# X-M3P1O5__main_V1_0.net
KiCad netlist of a schematic drawn in Altium Designer
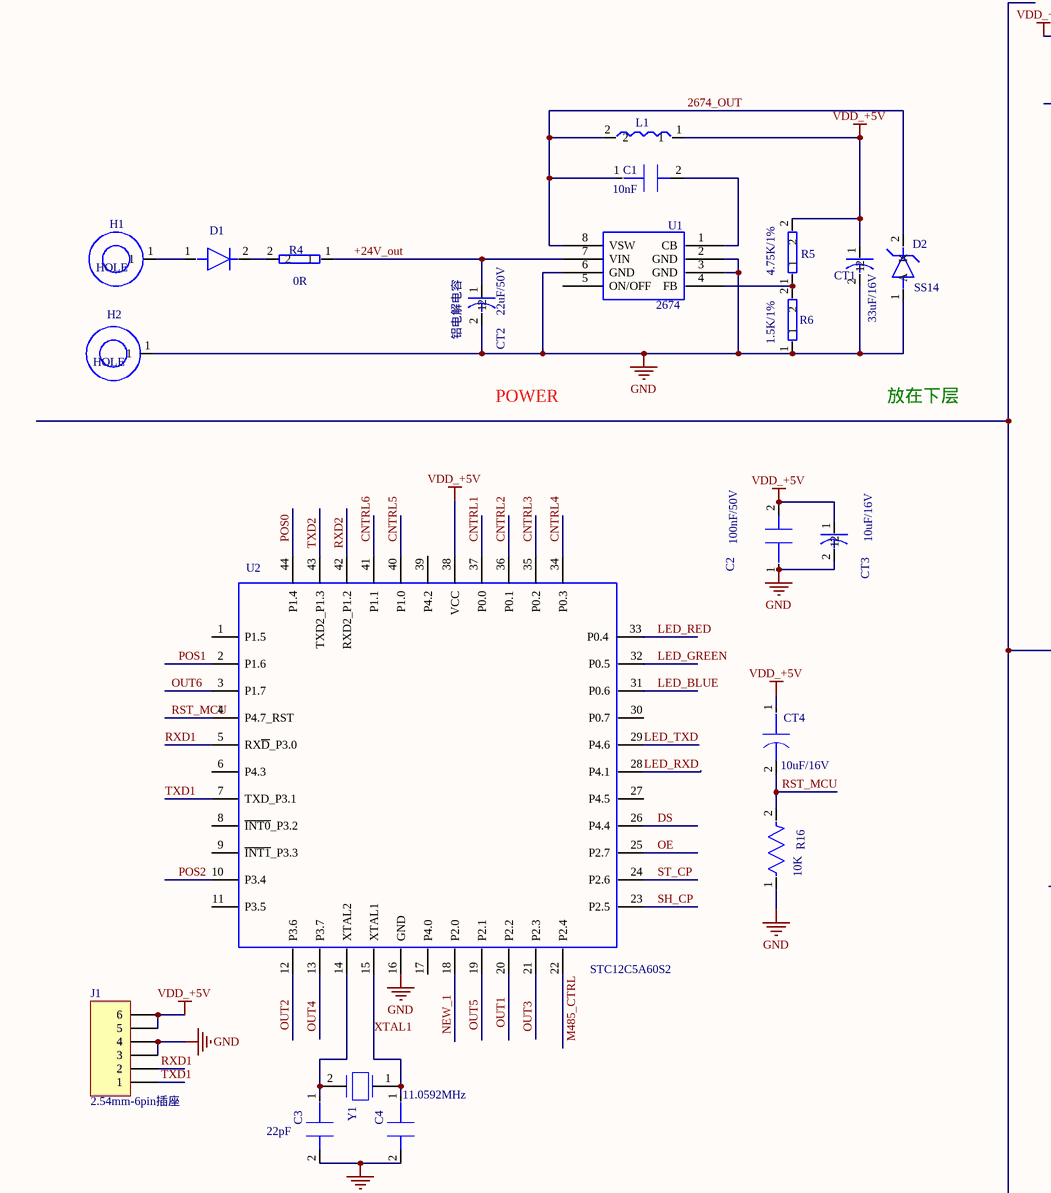
[diagram p0: X-M3P1O5__main_V1.0.SchDoc, top left]
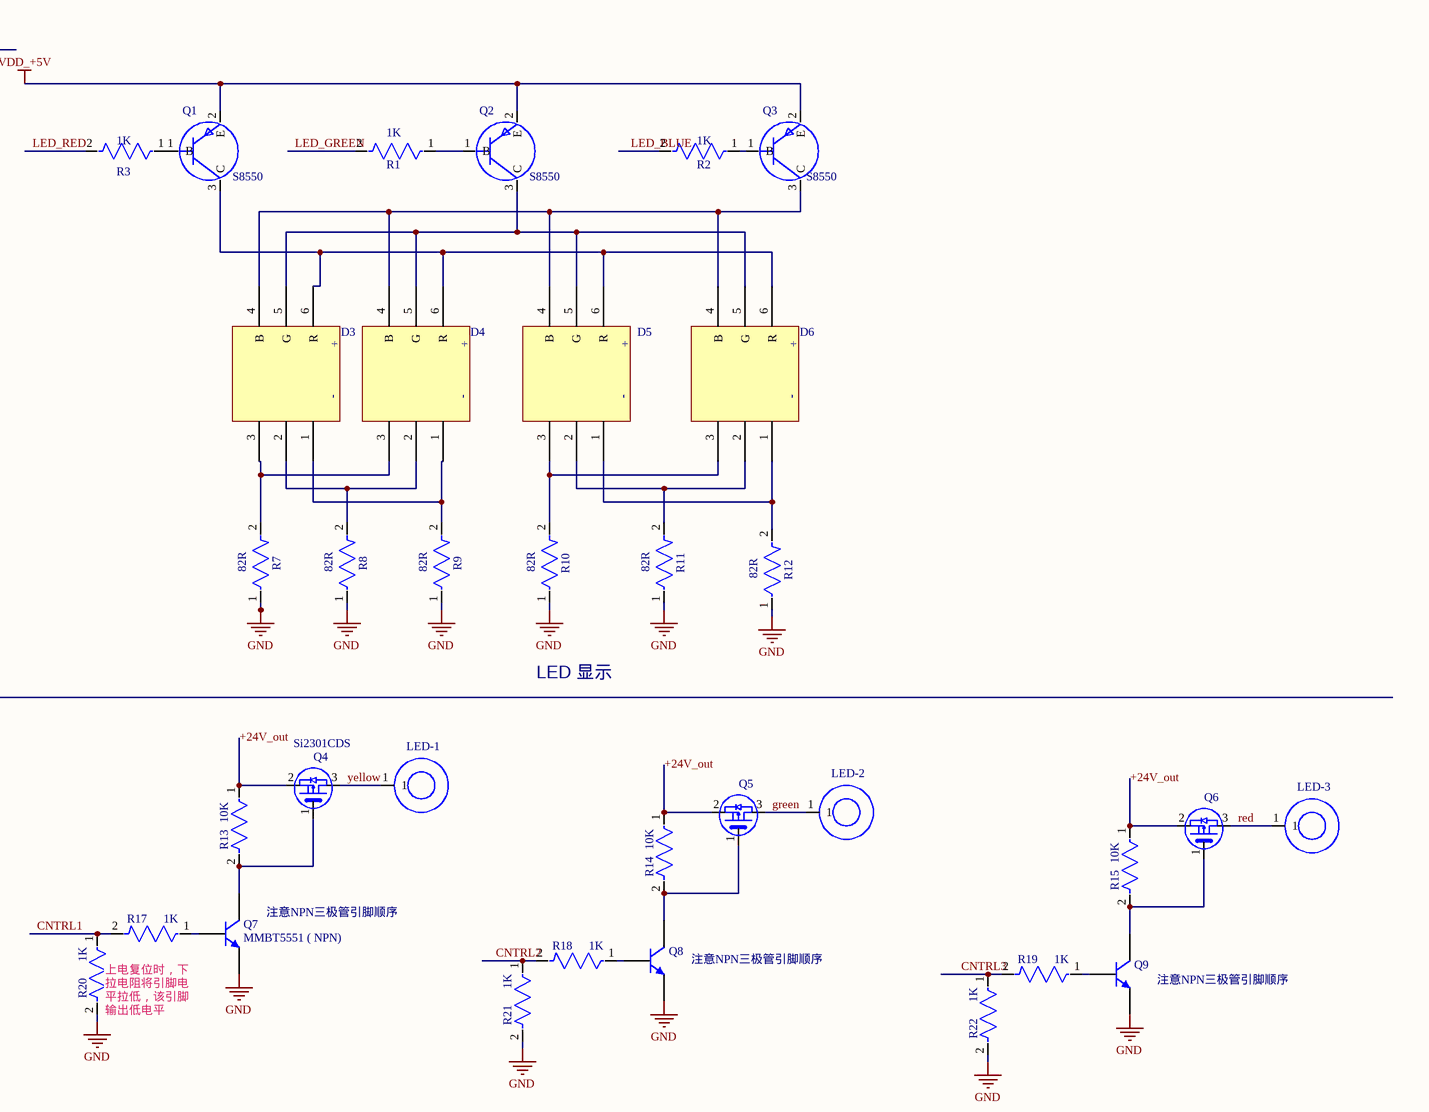
[diagram p1: X-M3P1O5__main_V1.0.SchDoc, top right]
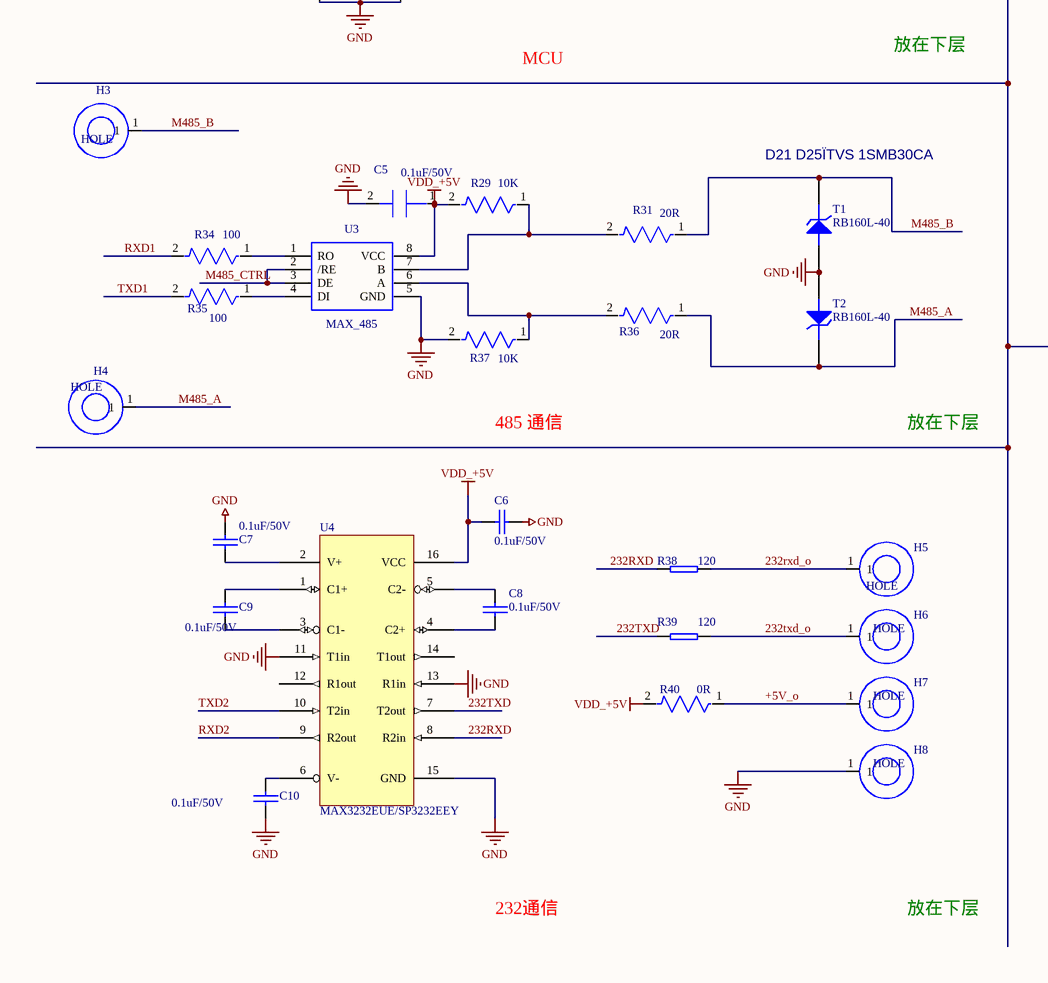
[diagram p2: X-M3P1O5__main_V1.0.SchDoc, bottom left]
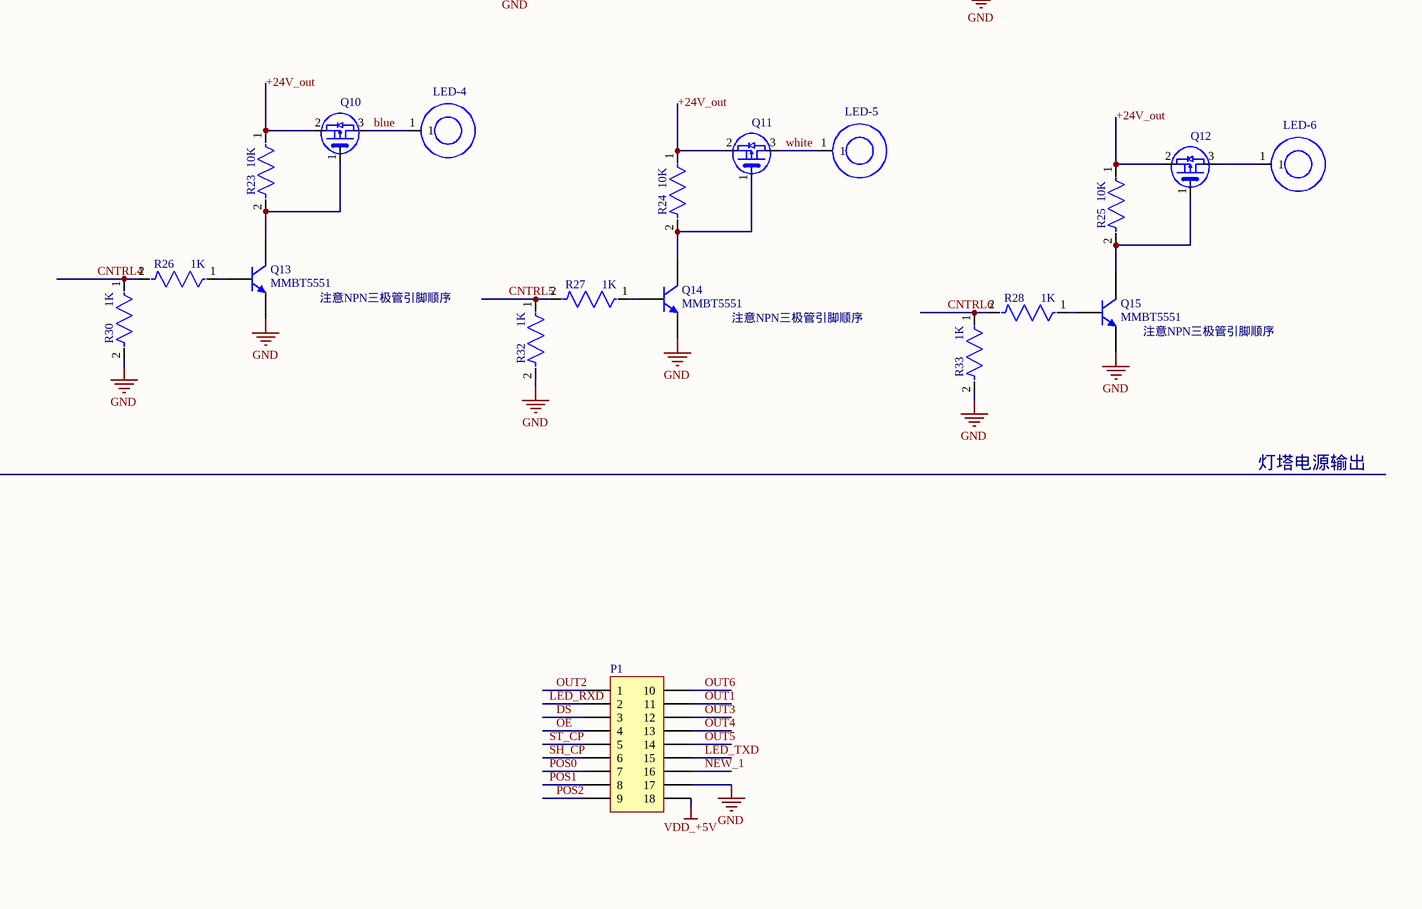
[diagram p3: X-M3P1O5__main_V1.0.SchDoc, bottom right]

(export (version "E")
  (design (tool "Eeschema 10.0.6"))
  (components
    (comp (ref "C1")
      (value "10nF")
      (footprint "MODBUS_V1.0:C0603")
      (description "SURFACE MOUNT CAPACITOR 0.031 X 0.061 INCHES")
      (fields (field (name "Comment") "CAP0603"))
      (libsource (lib "") (part "CAP0603_1"))
    )
    (comp (ref "C2")
      (value "100nF/50V")
      (footprint "MODBUS_V1.0:C0603")
      (description "SURFACE MOUNT CAPACITOR 0.031 X 0.061 INCHES")
      (fields (field (name "Comment") "CAP0603"))
      (libsource (lib "*") (part "CAP0603"))
    )
    (comp (ref "C3")
      (value "22pF")
      (footprint "C0603")
      (description "SURFACE MOUNT CAPACITOR 0.031 X 0.061 INCHES")
      (fields (field (name "Comment") "22pF/50V"))
      (libsource (lib "*") (part "CAP0603"))
    )
    (comp (ref "C4")
      (value "22pF/50V")
      (footprint "C0603")
      (description "SURFACE MOUNT CAPACITOR 0.031 X 0.061 INCHES")
      (libsource (lib "*") (part "CAP0603"))
    )
    (comp (ref "C5")
      (value "0.1uF/50V")
      (footprint "0603")
      (description "SURFACE MOUNT CAPACITOR 0.031 X 0.061 INCHES")
      (libsource (lib "") (part "CAP0603_1"))
    )
    (comp (ref "C6")
      (value "0.1uF/50V")
      (footprint "0603")
      (description "Capacitor")
      (libsource (lib "*") (part "CAP"))
    )
    (comp (ref "C7")
      (value "0.1uF/50V")
      (footprint "0603")
      (description "Capacitor")
      (libsource (lib "*") (part "CAP"))
    )
    (comp (ref "C8")
      (value "0.1uF/50V")
      (footprint "0603")
      (description "Capacitor")
      (libsource (lib "*") (part "CAP"))
    )
    (comp (ref "C9")
      (value "0.1uF/50V")
      (footprint "0603")
      (description "Capacitor")
      (libsource (lib "*") (part "CAP"))
    )
    (comp (ref "C10")
      (value "0.1uF/50V")
      (footprint "0603")
      (description "Capacitor")
      (libsource (lib "*") (part "CAP"))
    )
    (comp (ref "CT1")
      (value "33uF/16V")
      (footprint "MODBUS_V1.0:CT3528")
      (fields (field (name "Comment") "CE"))
      (libsource (lib "*") (part "CE"))
    )
    (comp (ref "CT2")
      (value "铝电解电容")
      (footprint "钱库:RB0.1")
      (fields (field (name "ALTIUM_VALUE") "22uF/50V"))
      (libsource (lib "*") (part "CE"))
    )
    (comp (ref "CT3") (value "10uF/16V") (footprint "钱库:1206C") (libsource (lib "*") (part "CE")))
    (comp (ref "CT4")
      (value "10uF/16V")
      (footprint "钱库:1206C")
      (description "SURFACE MOUNT CAPACITOR 0.048 X 0.079 INCHES")
      (libsource (lib "*") (part "CT"))
    )
    (comp (ref "D1")
      (value "M7")
      (footprint "SMB")
      (description "SURFACE MOUNT DIODE, MELF (SOD-80)")
      (libsource (lib "*") (part "DIO-MLL34"))
    )
    (comp (ref "D2") (value "SS14") (footprint "SMB") (libsource (lib "*") (part "DIOZ")))
    (comp (ref "D3")
      (value "5050RGB")
      (footprint "MODBUS_V1.0:5050RGB")
      (libsource (lib "MODBUS_V1.0") (part "5050RGB"))
    )
    (comp (ref "D4")
      (value "5050RGB")
      (footprint "MODBUS_V1.0:5050RGB")
      (libsource (lib "MODBUS_V1.0") (part "5050RGB"))
    )
    (comp (ref "D5")
      (value "5050RGB")
      (footprint "MODBUS_V1.0:5050RGB")
      (libsource (lib "MODBUS_V1.0") (part "5050RGB"))
    )
    (comp (ref "D6")
      (value "5050RGB")
      (footprint "MODBUS_V1.0:5050RGB")
      (libsource (lib "MODBUS_V1.0") (part "5050RGB"))
    )
    (comp (ref "H1") (value "HOLE") (footprint "HOLE_SMD") (libsource (lib "MODBUS_V1.0") (part "HOLE")))
    (comp (ref "H2") (value "HOLE") (footprint "HOLE_SMD") (libsource (lib "MODBUS_V1.0") (part "HOLE")))
    (comp (ref "H3") (value "HOLE") (footprint "HOLE_SMD") (libsource (lib "MODBUS_V1.0") (part "HOLE")))
    (comp (ref "H4") (value "HOLE") (footprint "HOLE_SMD") (libsource (lib "MODBUS_V1.0") (part "HOLE")))
    (comp (ref "H5") (value "HOLE") (footprint "HOLE_SMD") (libsource (lib "MODBUS_V1.0") (part "HOLE")))
    (comp (ref "H6") (value "HOLE") (footprint "HOLE_SMD") (libsource (lib "MODBUS_V1.0") (part "HOLE")))
    (comp (ref "H7") (value "HOLE") (footprint "HOLE_SMD") (libsource (lib "MODBUS_V1.0") (part "HOLE")))
    (comp (ref "H8") (value "HOLE") (footprint "HOLE_SMD") (libsource (lib "MODBUS_V1.0") (part "HOLE")))
    (comp (ref "J1")
      (value "2.54mm-6pin插座")
      (footprint "HDR1X6")
      (description "Header, 6-Pin")
      (fields (field (name "PUBLISHER") "Altium Limited"))
      (libsource (lib "Miscellaneous Connectors") (part "Header 6"))
    )
    (comp (ref "L1") (value "FB") (footprint "MODBUS_V1.0:L-6X6") (libsource (lib "*") (part "FB")))
    (comp (ref "LED-1") (value "LED_4") (footprint "HOLE_SMD") (libsource (lib "*") (part "HOLE")))
    (comp (ref "LED-2") (value "LED_4") (footprint "HOLE_SMD") (libsource (lib "*") (part "HOLE")))
    (comp (ref "LED-3") (value "LED_4") (footprint "HOLE_SMD") (libsource (lib "*") (part "HOLE")))
    (comp (ref "LED-4") (value "LED_4") (footprint "HOLE_SMD") (libsource (lib "*") (part "HOLE")))
    (comp (ref "LED-5") (value "LED_4") (footprint "HOLE_SMD") (libsource (lib "*") (part "HOLE")))
    (comp (ref "LED-6") (value "LED_4") (footprint "HOLE_SMD") (libsource (lib "*") (part "HOLE")))
    (comp (ref "P1")
      (value "Header 9X2A")
      (footprint "HDR2X9_CEN")
      (description "Header, 9-Pin, Dual row")
      (fields (field (name "PUBLISHER") "Altium Limited"))
      (libsource (lib "Miscellaneous Connectors") (part "Header 9X2A"))
    )
    (comp (ref "Q1")
      (value "S8550")
      (footprint "MODBUS_V1.0:SOT-23")
      (description "QUAD AMPLIFIER SWITCHING PNP SILICON TRANSISTOR")
      (fields (field (name "PART NUMBER") "2N3906"))
      (libsource (lib "*") (part "PNP(SOT-23)"))
    )
    (comp (ref "Q2")
      (value "S8550")
      (footprint "SOT-23")
      (description "QUAD AMPLIFIER SWITCHING PNP SILICON TRANSISTOR")
      (fields (field (name "PART NUMBER") "2N3906"))
      (libsource (lib "*") (part "S8550"))
    )
    (comp (ref "Q3")
      (value "S8550")
      (footprint "SOT-23")
      (description "QUAD AMPLIFIER SWITCHING PNP SILICON TRANSISTOR")
      (fields (field (name "PART NUMBER") "2N3906"))
      (libsource (lib "*") (part "S8550"))
    )
    (comp (ref "Q4") (value "Si2301CDS") (footprint "SOT-23") (libsource (lib "BATTERY") (part "P-MOSFET")))
    (comp (ref "Q5") (value "Si2301CDS") (footprint "SOT-23") (libsource (lib "BATTERY") (part "P-MOSFET")))
    (comp (ref "Q6") (value "Si2301CDS") (footprint "SOT-23") (libsource (lib "BATTERY") (part "P-MOSFET")))
    (comp (ref "Q7")
      (value "MMBT5551 ( NPN)")
      (footprint "SOT-23")
      (description "NPN Bipolar Transistor")
      (fields (field (name "PUBLISHER") "Altium Limited"))
      (libsource (lib "Miscellaneous Devices") (part "NPN"))
    )
    (comp (ref "Q8")
      (value "MMBT5551")
      (footprint "SOT-23")
      (description "NPN Bipolar Transistor")
      (fields (field (name "PUBLISHER") "Altium Limited"))
      (libsource (lib "Miscellaneous Devices") (part "NPN"))
    )
    (comp (ref "Q9")
      (value "MMBT5551")
      (footprint "SOT-23")
      (description "NPN Bipolar Transistor")
      (fields (field (name "PUBLISHER") "Altium Limited"))
      (libsource (lib "Miscellaneous Devices") (part "NPN"))
    )
    (comp (ref "Q10") (value "Si2301CDS") (footprint "SOT-23") (libsource (lib "BATTERY") (part "P-MOSFET")))
    (comp (ref "Q11") (value "Si2301CDS") (footprint "SOT-23") (libsource (lib "BATTERY") (part "P-MOSFET")))
    (comp (ref "Q12") (value "Si2301CDS") (footprint "SOT-23") (libsource (lib "BATTERY") (part "P-MOSFET")))
    (comp (ref "Q13")
      (value "MMBT5551")
      (footprint "SOT-23")
      (description "NPN Bipolar Transistor")
      (fields (field (name "PUBLISHER") "Altium Limited"))
      (libsource (lib "Miscellaneous Devices") (part "NPN"))
    )
    (comp (ref "Q14")
      (value "MMBT5551")
      (footprint "SOT-23")
      (description "NPN Bipolar Transistor")
      (fields (field (name "PUBLISHER") "Altium Limited"))
      (libsource (lib "Miscellaneous Devices") (part "NPN"))
    )
    (comp (ref "Q15")
      (value "MMBT5551")
      (footprint "SOT-23")
      (description "NPN Bipolar Transistor")
      (fields (field (name "PUBLISHER") "Altium Limited"))
      (libsource (lib "Miscellaneous Devices") (part "NPN"))
    )
    (comp (ref "R1")
      (value "1K")
      (footprint "MODBUS_V1.0:R0603")
      (description "SURFACE MOUNT RESISTOR 0.031 X 0.061 INCHES, 1/10W")
      (fields (field (name "Comment") "RES0603"))
      (libsource (lib "*") (part "RES0603"))
    )
    (comp (ref "R2")
      (value "1K")
      (footprint "MODBUS_V1.0:R0603")
      (description "SURFACE MOUNT RESISTOR 0.031 X 0.061 INCHES, 1/10W")
      (fields (field (name "Comment") "RES0603"))
      (libsource (lib "*") (part "RES0603"))
    )
    (comp (ref "R3")
      (value "1K")
      (footprint "MODBUS_V1.0:R0603")
      (description "SURFACE MOUNT RESISTOR 0.031 X 0.061 INCHES, 1/10W")
      (fields (field (name "Comment") "RES0603"))
      (libsource (lib "*") (part "RES0603"))
    )
    (comp (ref "R4") (value "0R") (footprint "钱库:1206") (libsource (lib "") (part "RES_1")))
    (comp (ref "R5") (value "4.75K/1%") (footprint "MODBUS_V1.0:R0603") (libsource (lib "*") (part "RES")))
    (comp (ref "R6") (value "1.5K/1%") (footprint "MODBUS_V1.0:R0603") (libsource (lib "*") (part "RES")))
    (comp (ref "R7")
      (value "82R")
      (footprint "1206")
      (description "SURFACE MOUNT RESISTOR 0.031 X 0.061 INCHES, 1/10W")
      (libsource (lib "*") (part "RES0603"))
    )
    (comp (ref "R8")
      (value "82R")
      (footprint "钱库:1206")
      (description "SURFACE MOUNT RESISTOR 0.031 X 0.061 INCHES, 1/10W")
      (libsource (lib "*") (part "RES0603"))
    )
    (comp (ref "R9")
      (value "82R")
      (footprint "钱库:1206")
      (description "SURFACE MOUNT RESISTOR 0.031 X 0.061 INCHES, 1/10W")
      (libsource (lib "*") (part "RES0603"))
    )
    (comp (ref "R10")
      (value "82R")
      (footprint "钱库:1206")
      (description "SURFACE MOUNT RESISTOR 0.031 X 0.061 INCHES, 1/10W")
      (libsource (lib "*") (part "RES0603"))
    )
    (comp (ref "R11")
      (value "82R")
      (footprint "钱库:1206")
      (description "SURFACE MOUNT RESISTOR 0.031 X 0.061 INCHES, 1/10W")
      (libsource (lib "*") (part "RES0603"))
    )
    (comp (ref "R12")
      (value "82R")
      (footprint "钱库:1206")
      (description "SURFACE MOUNT RESISTOR 0.031 X 0.061 INCHES, 1/10W")
      (libsource (lib "*") (part "RES0603"))
    )
    (comp (ref "R13")
      (value "10K")
      (footprint "R0603")
      (description "SURFACE MOUNT RESISTOR 0.031 X 0.061 INCHES, 1/10W")
      (libsource (lib "*") (part "RES0603"))
    )
    (comp (ref "R14")
      (value "10K")
      (footprint "R0603")
      (description "SURFACE MOUNT RESISTOR 0.031 X 0.061 INCHES, 1/10W")
      (libsource (lib "*") (part "RES0603"))
    )
    (comp (ref "R15")
      (value "10K")
      (footprint "R0603")
      (description "SURFACE MOUNT RESISTOR 0.031 X 0.061 INCHES, 1/10W")
      (libsource (lib "*") (part "RES0603"))
    )
    (comp (ref "R16")
      (value "10K")
      (footprint "R0603")
      (description "SURFACE MOUNT RESISTOR 0.031 X 0.061 INCHES, 1/10W")
      (libsource (lib "*") (part "RES0603"))
    )
    (comp (ref "R17")
      (value "1K")
      (footprint "R0603")
      (description "SURFACE MOUNT RESISTOR 0.031 X 0.061 INCHES, 1/10W")
      (libsource (lib "*") (part "RES0603"))
    )
    (comp (ref "R18")
      (value "1K")
      (footprint "R0603")
      (description "SURFACE MOUNT RESISTOR 0.031 X 0.061 INCHES, 1/10W")
      (libsource (lib "*") (part "RES0603"))
    )
    (comp (ref "R19")
      (value "1K")
      (footprint "R0603")
      (description "SURFACE MOUNT RESISTOR 0.031 X 0.061 INCHES, 1/10W")
      (libsource (lib "*") (part "RES0603"))
    )
    (comp (ref "R20")
      (value "1K")
      (footprint "R0603")
      (description "SURFACE MOUNT RESISTOR 0.031 X 0.061 INCHES, 1/10W")
      (libsource (lib "*") (part "RES0603"))
    )
    (comp (ref "R21")
      (value "1K")
      (footprint "R0603")
      (description "SURFACE MOUNT RESISTOR 0.031 X 0.061 INCHES, 1/10W")
      (libsource (lib "*") (part "RES0603"))
    )
    (comp (ref "R22")
      (value "1K")
      (footprint "R0603")
      (description "SURFACE MOUNT RESISTOR 0.031 X 0.061 INCHES, 1/10W")
      (libsource (lib "*") (part "RES0603"))
    )
    (comp (ref "R23")
      (value "10K")
      (footprint "R0603")
      (description "SURFACE MOUNT RESISTOR 0.031 X 0.061 INCHES, 1/10W")
      (libsource (lib "*") (part "RES0603"))
    )
    (comp (ref "R24")
      (value "10K")
      (footprint "R0603")
      (description "SURFACE MOUNT RESISTOR 0.031 X 0.061 INCHES, 1/10W")
      (libsource (lib "*") (part "RES0603"))
    )
    (comp (ref "R25")
      (value "10K")
      (footprint "R0603")
      (description "SURFACE MOUNT RESISTOR 0.031 X 0.061 INCHES, 1/10W")
      (libsource (lib "*") (part "RES0603"))
    )
    (comp (ref "R26")
      (value "1K")
      (footprint "R0603")
      (description "SURFACE MOUNT RESISTOR 0.031 X 0.061 INCHES, 1/10W")
      (libsource (lib "*") (part "RES0603"))
    )
    (comp (ref "R27")
      (value "1K")
      (footprint "R0603")
      (description "SURFACE MOUNT RESISTOR 0.031 X 0.061 INCHES, 1/10W")
      (libsource (lib "*") (part "RES0603"))
    )
    (comp (ref "R28")
      (value "1K")
      (footprint "R0603")
      (description "SURFACE MOUNT RESISTOR 0.031 X 0.061 INCHES, 1/10W")
      (libsource (lib "*") (part "RES0603"))
    )
    (comp (ref "R29")
      (value "10K")
      (footprint "R0603")
      (description "SURFACE MOUNT RESISTOR 0.031 X 0.061 INCHES, 1/10W")
      (libsource (lib "*") (part "RES0603"))
    )
    (comp (ref "R30")
      (value "1K")
      (footprint "R0603")
      (description "SURFACE MOUNT RESISTOR 0.031 X 0.061 INCHES, 1/10W")
      (libsource (lib "*") (part "RES0603"))
    )
    (comp (ref "R31")
      (value "20R")
      (footprint "MODBUS_V2.0:1206")
      (description "SURFACE MOUNT RESISTOR 0.031 X 0.061 INCHES, 1/10W")
      (libsource (lib "*") (part "RES0603"))
    )
    (comp (ref "R32")
      (value "1K")
      (footprint "R0603")
      (description "SURFACE MOUNT RESISTOR 0.031 X 0.061 INCHES, 1/10W")
      (libsource (lib "*") (part "RES0603"))
    )
    (comp (ref "R33")
      (value "1K")
      (footprint "R0603")
      (description "SURFACE MOUNT RESISTOR 0.031 X 0.061 INCHES, 1/10W")
      (libsource (lib "*") (part "RES0603"))
    )
    (comp (ref "R34")
      (value "100")
      (footprint "R0603")
      (description "SURFACE MOUNT RESISTOR 0.031 X 0.061 INCHES, 1/10W")
      (libsource (lib "*") (part "RES0603"))
    )
    (comp (ref "R35")
      (value "100")
      (footprint "R0603")
      (description "SURFACE MOUNT RESISTOR 0.031 X 0.061 INCHES, 1/10W")
      (libsource (lib "*") (part "RES0603"))
    )
    (comp (ref "R36")
      (value "20R")
      (footprint "2010")
      (description "SURFACE MOUNT RESISTOR 0.031 X 0.061 INCHES, 1/10W")
      (libsource (lib "*") (part "RES0603"))
    )
    (comp (ref "R37")
      (value "10K")
      (footprint "R0603")
      (description "SURFACE MOUNT RESISTOR 0.031 X 0.061 INCHES, 1/10W")
      (libsource (lib "*") (part "RES0603"))
    )
    (comp (ref "R38") (value "120") (footprint "R0603") (libsource (lib "*") (part "Component_1")))
    (comp (ref "R39") (value "120") (footprint "R0603") (libsource (lib "*") (part "Component_1")))
    (comp (ref "R40")
      (value "0R")
      (footprint "1206")
      (description "SURFACE MOUNT RESISTOR 0.031 X 0.061 INCHES, 1/10W")
      (libsource (lib "*") (part "RES0603"))
    )
    (comp (ref "T1")
      (value "RB160L-40")
      (footprint "HSMA")
      (description "Zener Diode")
      (libsource (lib "*") (part "ZENER3"))
    )
    (comp (ref "T2")
      (value "RB160L-40")
      (footprint "HSMA")
      (description "Zener Diode")
      (libsource (lib "*") (part "ZENER3"))
    )
    (comp (ref "U1")
      (value "2674")
      (footprint "MODBUS_V1.0:SO-1.27-9/4.0")
      (libsource (lib "*") (part "2674"))
    )
    (comp (ref "U2")
      (value "STC12C5A60S2")
      (footprint "STC_LQFP44")
      (libsource (lib "MODBUS") (part "STC12C5A60S2_LQFP-44"))
    )
    (comp (ref "U3") (value "MAX_485") (footprint "SO-1.27-8/4.0") (libsource (lib "*") (part "MAX_485")))
    (comp (ref "U4")
      (value "MAX3232EUE/SP3232EEY")
      (footprint "MODBUS_V1.0:TSOP16")
      (description "RS232 Transceiver")
      (libsource (lib "*") (part "ST3232"))
    )
    (comp (ref "Y1")
      (value "11.0592MHz")
      (footprint "49US")
      (description "CRYSTAL")
      (libsource (lib "*") (part "XTAL-1"))
    )
  )
  (nets
    (net (code "1") (name "/+5V_o") (class "Default")
      (node (ref "H7") (pin "1") (pinfunction "1_1") (pintype "passive"))
      (node (ref "R40") (pin "1") (pintype "passive"))
    )
    (net (code "2") (name "/+24V_out") (class "Default")
      (node (ref "CT2") (pin "1") (pinfunction "1_1") (pintype "passive"))
      (node (ref "Q10") (pin "2") (pinfunction "S_2") (pintype "passive"))
      (node (ref "Q11") (pin "2") (pinfunction "S_2") (pintype "passive"))
      (node (ref "Q12") (pin "2") (pinfunction "S_2") (pintype "passive"))
      (node (ref "Q4") (pin "2") (pinfunction "S_2") (pintype "passive"))
      (node (ref "Q5") (pin "2") (pinfunction "S_2") (pintype "passive"))
      (node (ref "Q6") (pin "2") (pinfunction "S_2") (pintype "passive"))
      (node (ref "R13") (pin "1") (pintype "passive"))
      (node (ref "R14") (pin "1") (pintype "passive"))
      (node (ref "R15") (pin "1") (pintype "passive"))
      (node (ref "R23") (pin "1") (pintype "passive"))
      (node (ref "R24") (pin "1") (pintype "passive"))
      (node (ref "R25") (pin "1") (pintype "passive"))
      (node (ref "R4") (pin "1") (pinfunction "1_1") (pintype "passive"))
      (node (ref "U1") (pin "7") (pinfunction "VIN_7") (pintype "passive"))
    )
    (net (code "3") (name "/232RXD") (class "Default")
      (node (ref "R38") (pin "2") (pintype "passive"))
      (node (ref "U4") (pin "8") (pinfunction "R2in_8") (pintype "input"))
    )
    (net (code "4") (name "/232TXD") (class "Default")
      (node (ref "R39") (pin "2") (pintype "passive"))
      (node (ref "U4") (pin "7") (pinfunction "T2out_7") (pintype "output"))
    )
    (net (code "5") (name "/232rxd_o") (class "Default")
      (node (ref "H5") (pin "1") (pinfunction "1_1") (pintype "passive"))
      (node (ref "R38") (pin "1") (pintype "passive"))
    )
    (net (code "6") (name "/232txd_o") (class "Default")
      (node (ref "H6") (pin "1") (pinfunction "1_1") (pintype "passive"))
      (node (ref "R39") (pin "1") (pintype "passive"))
    )
    (net (code "7") (name "/2674_OUT") (class "Default")
      (node (ref "C1") (pin "1") (pintype "passive"))
      (node (ref "D2") (pin "2") (pinfunction "K_2") (pintype "passive"))
      (node (ref "L1") (pin "2") (pinfunction "2_2") (pintype "passive"))
      (node (ref "U1") (pin "8") (pinfunction "VSW_8") (pintype "passive"))
    )
    (net (code "8") (name "/CNTRL1") (class "Default")
      (node (ref "R17") (pin "2") (pintype "passive"))
      (node (ref "R20") (pin "1") (pintype "passive"))
      (node (ref "U2") (pin "37") (pinfunction "P0.0_37") (pintype "passive"))
    )
    (net (code "9") (name "/CNTRL2") (class "Default")
      (node (ref "R18") (pin "2") (pintype "passive"))
      (node (ref "R21") (pin "1") (pintype "passive"))
      (node (ref "U2") (pin "36") (pinfunction "P0.1_36") (pintype "passive"))
    )
    (net (code "10") (name "/CNTRL3") (class "Default")
      (node (ref "R19") (pin "2") (pintype "passive"))
      (node (ref "R22") (pin "1") (pintype "passive"))
      (node (ref "U2") (pin "35") (pinfunction "P0.2_35") (pintype "passive"))
    )
    (net (code "11") (name "/CNTRL4") (class "Default")
      (node (ref "R26") (pin "2") (pintype "passive"))
      (node (ref "R30") (pin "1") (pintype "passive"))
      (node (ref "U2") (pin "34") (pinfunction "P0.3_34") (pintype "passive"))
    )
    (net (code "12") (name "/CNTRL5") (class "Default")
      (node (ref "R27") (pin "2") (pintype "passive"))
      (node (ref "R32") (pin "1") (pintype "passive"))
      (node (ref "U2") (pin "40") (pinfunction "P1.0_40") (pintype "passive"))
    )
    (net (code "13") (name "/CNTRL6") (class "Default")
      (node (ref "R28") (pin "2") (pintype "passive"))
      (node (ref "R33") (pin "1") (pintype "passive"))
      (node (ref "U2") (pin "41") (pinfunction "P1.1_41") (pintype "passive"))
    )
    (net (code "14") (name "/DS") (class "Default")
      (node (ref "P1") (pin "3") (pinfunction "3_3") (pintype "passive"))
      (node (ref "U2") (pin "26") (pinfunction "P4.4_26") (pintype "passive"))
    )
    (net (code "15") (name "/LED_BLUE") (class "Default")
      (node (ref "R2") (pin "2") (pintype "passive"))
      (node (ref "U2") (pin "31") (pinfunction "P0.6_31") (pintype "passive"))
    )
    (net (code "16") (name "/LED_GREEN") (class "Default")
      (node (ref "R1") (pin "2") (pintype "passive"))
      (node (ref "U2") (pin "32") (pinfunction "P0.5_32") (pintype "passive"))
    )
    (net (code "17") (name "/LED_RED") (class "Default")
      (node (ref "R3") (pin "2") (pintype "passive"))
      (node (ref "U2") (pin "33") (pinfunction "P0.4_33") (pintype "passive"))
    )
    (net (code "18") (name "/LED_RXD") (class "Default")
      (node (ref "P1") (pin "2") (pinfunction "2_2") (pintype "passive"))
      (node (ref "U2") (pin "28") (pinfunction "P4.1_28") (pintype "passive"))
    )
    (net (code "19") (name "/LED_TXD") (class "Default")
      (node (ref "P1") (pin "15") (pinfunction "15_15") (pintype "passive"))
      (node (ref "U2") (pin "29") (pinfunction "P4.6_29") (pintype "passive"))
    )
    (net (code "20") (name "/M485_A") (class "Default")
      (node (ref "H4") (pin "1") (pinfunction "1_1") (pintype "passive"))
      (node (ref "R36") (pin "1") (pintype "passive"))
      (node (ref "T2") (pin "2") (pinfunction "K_2") (pintype "passive"))
    )
    (net (code "21") (name "/M485_B") (class "Default")
      (node (ref "H3") (pin "1") (pinfunction "1_1") (pintype "passive"))
      (node (ref "R31") (pin "1") (pintype "passive"))
      (node (ref "T1") (pin "2") (pinfunction "K_2") (pintype "passive"))
    )
    (net (code "22") (name "/M485_CTRL") (class "Default")
      (node (ref "U2") (pin "22") (pinfunction "P2.4_22") (pintype "passive"))
      (node (ref "U3") (pin "2") (pinfunction "/RE_2") (pintype "passive"))
      (node (ref "U3") (pin "3") (pinfunction "DE_3") (pintype "passive"))
    )
    (net (code "23") (name "/NEW_1") (class "Default")
      (node (ref "P1") (pin "16") (pinfunction "16_16") (pintype "passive"))
      (node (ref "U2") (pin "18") (pinfunction "P2.0_18") (pintype "passive"))
    )
    (net (code "24") (name "/OE") (class "Default")
      (node (ref "P1") (pin "4") (pinfunction "4_4") (pintype "passive"))
      (node (ref "U2") (pin "25") (pinfunction "P2.7_25") (pintype "passive"))
    )
    (net (code "25") (name "/OUT1") (class "Default")
      (node (ref "P1") (pin "11") (pinfunction "11_11") (pintype "passive"))
      (node (ref "U2") (pin "20") (pinfunction "P2.2_20") (pintype "passive"))
    )
    (net (code "26") (name "/OUT2") (class "Default")
      (node (ref "P1") (pin "1") (pinfunction "1_1") (pintype "passive"))
      (node (ref "U2") (pin "12") (pinfunction "P3.6_12") (pintype "passive"))
    )
    (net (code "27") (name "/OUT3") (class "Default")
      (node (ref "P1") (pin "12") (pinfunction "12_12") (pintype "passive"))
      (node (ref "U2") (pin "21") (pinfunction "P2.3_21") (pintype "passive"))
    )
    (net (code "28") (name "/OUT4") (class "Default")
      (node (ref "P1") (pin "13") (pinfunction "13_13") (pintype "passive"))
      (node (ref "U2") (pin "13") (pinfunction "P3.7_13") (pintype "passive"))
    )
    (net (code "29") (name "/OUT5") (class "Default")
      (node (ref "P1") (pin "14") (pinfunction "14_14") (pintype "passive"))
      (node (ref "U2") (pin "19") (pinfunction "P2.1_19") (pintype "passive"))
    )
    (net (code "30") (name "/OUT6") (class "Default")
      (node (ref "P1") (pin "10") (pinfunction "10_10") (pintype "passive"))
      (node (ref "U2") (pin "3") (pinfunction "P1.7_3") (pintype "passive"))
    )
    (net (code "31") (name "/POS0") (class "Default")
      (node (ref "P1") (pin "7") (pinfunction "7_7") (pintype "passive"))
      (node (ref "U2") (pin "44") (pinfunction "P1.4_44") (pintype "passive"))
    )
    (net (code "32") (name "/POS1") (class "Default")
      (node (ref "P1") (pin "8") (pinfunction "8_8") (pintype "passive"))
      (node (ref "U2") (pin "2") (pinfunction "P1.6_2") (pintype "passive"))
    )
    (net (code "33") (name "/POS2") (class "Default")
      (node (ref "P1") (pin "9") (pinfunction "9_9") (pintype "passive"))
      (node (ref "U2") (pin "10") (pinfunction "P3.4_10") (pintype "passive"))
    )
    (net (code "34") (name "/RST_MCU") (class "Default")
      (node (ref "CT4") (pin "2") (pintype "passive"))
      (node (ref "R16") (pin "2") (pintype "passive"))
      (node (ref "U2") (pin "4") (pinfunction "P4.7_RST_4") (pintype "passive"))
    )
    (net (code "35") (name "/RXD1") (class "Default")
      (node (ref "J1") (pin "2") (pinfunction "2_2") (pintype "passive"))
      (node (ref "R34") (pin "2") (pintype "passive"))
      (node (ref "U2") (pin "5") (pinfunction "RX~{D}_P3.0_5") (pintype "passive"))
    )
    (net (code "36") (name "/RXD2") (class "Default")
      (node (ref "U2") (pin "42") (pinfunction "RXD2_P1.2_42") (pintype "passive"))
      (node (ref "U4") (pin "9") (pinfunction "R2out_9") (pintype "output"))
    )
    (net (code "37") (name "/SH_CP") (class "Default")
      (node (ref "P1") (pin "6") (pinfunction "6_6") (pintype "passive"))
      (node (ref "U2") (pin "23") (pinfunction "P2.5_23") (pintype "passive"))
    )
    (net (code "38") (name "/ST_CP") (class "Default")
      (node (ref "P1") (pin "5") (pinfunction "5_5") (pintype "passive"))
      (node (ref "U2") (pin "24") (pinfunction "P2.6_24") (pintype "passive"))
    )
    (net (code "39") (name "/TXD1") (class "Default")
      (node (ref "J1") (pin "1") (pinfunction "1_1") (pintype "passive"))
      (node (ref "R35") (pin "2") (pintype "passive"))
      (node (ref "U2") (pin "7") (pinfunction "TXD_P3.1_7") (pintype "passive"))
    )
    (net (code "40") (name "/TXD2") (class "Default")
      (node (ref "U2") (pin "43") (pinfunction "TXD2_P1.3_43") (pintype "passive"))
      (node (ref "U4") (pin "10") (pinfunction "T2in_10") (pintype "input"))
    )
    (net (code "41") (name "/XTAL1") (class "Default")
      (node (ref "C4") (pin "1") (pintype "passive"))
      (node (ref "U2") (pin "15") (pinfunction "XTAL1_15") (pintype "passive"))
      (node (ref "Y1") (pin "1") (pintype "passive"))
    )
    (net (code "42") (name "/blue") (class "Default")
      (node (ref "LED-4") (pin "1") (pinfunction "1_1") (pintype "passive"))
      (node (ref "Q10") (pin "3") (pinfunction "D_3") (pintype "passive"))
    )
    (net (code "43") (name "/green") (class "Default")
      (node (ref "LED-2") (pin "1") (pinfunction "1_1") (pintype "passive"))
      (node (ref "Q5") (pin "3") (pinfunction "D_3") (pintype "passive"))
    )
    (net (code "44") (name "/red") (class "Default")
      (node (ref "LED-3") (pin "1") (pinfunction "1_1") (pintype "passive"))
      (node (ref "Q6") (pin "3") (pinfunction "D_3") (pintype "passive"))
    )
    (net (code "45") (name "/white") (class "Default")
      (node (ref "LED-5") (pin "1") (pinfunction "1_1") (pintype "passive"))
      (node (ref "Q11") (pin "3") (pinfunction "D_3") (pintype "passive"))
    )
    (net (code "46") (name "/yellow") (class "Default")
      (node (ref "LED-1") (pin "1") (pinfunction "1_1") (pintype "passive"))
      (node (ref "Q4") (pin "3") (pinfunction "D_3") (pintype "passive"))
    )
    (net (code "47") (name "GND") (class "Default")
      (node (ref "C10") (pin "1") (pinfunction "1_1") (pintype "passive"))
      (node (ref "C2") (pin "1") (pintype "passive"))
      (node (ref "C3") (pin "2") (pintype "passive"))
      (node (ref "C4") (pin "2") (pintype "passive"))
      (node (ref "C5") (pin "2") (pintype "passive"))
      (node (ref "C6") (pin "1") (pinfunction "1_1") (pintype "passive"))
      (node (ref "C7") (pin "1") (pinfunction "1_1") (pintype "passive"))
      (node (ref "CT1") (pin "2") (pinfunction "2_2") (pintype "passive"))
      (node (ref "CT2") (pin "2") (pinfunction "2_2") (pintype "passive"))
      (node (ref "CT3") (pin "2") (pinfunction "2_2") (pintype "passive"))
      (node (ref "D2") (pin "1") (pinfunction "A_1") (pintype "passive"))
      (node (ref "H2") (pin "1") (pinfunction "1_1") (pintype "passive"))
      (node (ref "H8") (pin "1") (pinfunction "1_1") (pintype "passive"))
      (node (ref "J1") (pin "3") (pinfunction "3_3") (pintype "passive"))
      (node (ref "J1") (pin "4") (pinfunction "4_4") (pintype "passive"))
      (node (ref "P1") (pin "17") (pinfunction "17_17") (pintype "passive"))
      (node (ref "Q13") (pin "2") (pinfunction "E_2") (pintype "passive"))
      (node (ref "Q14") (pin "2") (pinfunction "E_2") (pintype "passive"))
      (node (ref "Q15") (pin "2") (pinfunction "E_2") (pintype "passive"))
      (node (ref "Q7") (pin "2") (pinfunction "E_2") (pintype "passive"))
      (node (ref "Q8") (pin "2") (pinfunction "E_2") (pintype "passive"))
      (node (ref "Q9") (pin "2") (pinfunction "E_2") (pintype "passive"))
      (node (ref "R10") (pin "1") (pintype "passive"))
      (node (ref "R11") (pin "1") (pintype "passive"))
      (node (ref "R12") (pin "1") (pintype "passive"))
      (node (ref "R16") (pin "1") (pintype "passive"))
      (node (ref "R20") (pin "2") (pintype "passive"))
      (node (ref "R21") (pin "2") (pintype "passive"))
      (node (ref "R22") (pin "2") (pintype "passive"))
      (node (ref "R30") (pin "2") (pintype "passive"))
      (node (ref "R32") (pin "2") (pintype "passive"))
      (node (ref "R33") (pin "2") (pintype "passive"))
      (node (ref "R37") (pin "2") (pintype "passive"))
      (node (ref "R6") (pin "1") (pinfunction "1_1") (pintype "passive"))
      (node (ref "R7") (pin "1") (pintype "passive"))
      (node (ref "R8") (pin "1") (pintype "passive"))
      (node (ref "R9") (pin "1") (pintype "passive"))
      (node (ref "T1") (pin "1") (pinfunction "A_1") (pintype "passive"))
      (node (ref "T2") (pin "1") (pinfunction "A_1") (pintype "passive"))
      (node (ref "U1") (pin "2") (pinfunction "GND_2") (pintype "passive"))
      (node (ref "U1") (pin "3") (pinfunction "GND_3") (pintype "passive"))
      (node (ref "U1") (pin "6") (pinfunction "GND_6") (pintype "passive"))
      (node (ref "U2") (pin "16") (pinfunction "GND_16") (pintype "passive"))
      (node (ref "U3") (pin "5") (pinfunction "GND_5") (pintype "passive"))
      (node (ref "U4") (pin "11") (pinfunction "T1in_11") (pintype "input"))
      (node (ref "U4") (pin "13") (pinfunction "R1in_13") (pintype "input"))
      (node (ref "U4") (pin "15") (pinfunction "GND_15") (pintype "passive"))
    )
    (net (code "48") (name "Net-(D1-Pad1)") (class "Default")
      (node (ref "D1") (pin "1") (pintype "passive"))
      (node (ref "H1") (pin "1") (pinfunction "1_1") (pintype "passive"))
    )
    (net (code "49") (name "Net-(D1-Pad2)") (class "Default")
      (node (ref "D1") (pin "2") (pintype "passive"))
      (node (ref "R4") (pin "2") (pinfunction "2_2") (pintype "passive"))
    )
    (net (code "50") (name "Net-(D3-B)") (class "Default")
      (node (ref "D3") (pin "4") (pinfunction "B_4") (pintype "passive"))
      (node (ref "D4") (pin "4") (pinfunction "B_4") (pintype "passive"))
      (node (ref "D5") (pin "4") (pinfunction "B_4") (pintype "passive"))
      (node (ref "D6") (pin "4") (pinfunction "B_4") (pintype "passive"))
      (node (ref "Q3") (pin "3") (pinfunction "C_3") (pintype "passive"))
    )
    (net (code "51") (name "Net-(D3-G)") (class "Default")
      (node (ref "D3") (pin "5") (pinfunction "G_5") (pintype "passive"))
      (node (ref "D4") (pin "5") (pinfunction "G_5") (pintype "passive"))
      (node (ref "D5") (pin "5") (pinfunction "G_5") (pintype "passive"))
      (node (ref "D6") (pin "5") (pinfunction "G_5") (pintype "passive"))
      (node (ref "Q2") (pin "3") (pinfunction "C_3") (pintype "passive"))
    )
    (net (code "52") (name "Net-(D3-Pad1)") (class "Default")
      (node (ref "D3") (pin "1") (pintype "passive"))
      (node (ref "D4") (pin "1") (pintype "passive"))
      (node (ref "R9") (pin "2") (pintype "passive"))
    )
    (net (code "53") (name "Net-(D3-Pad2)") (class "Default")
      (node (ref "D3") (pin "2") (pintype "passive"))
      (node (ref "D4") (pin "2") (pintype "passive"))
      (node (ref "R8") (pin "2") (pintype "passive"))
    )
    (net (code "54") (name "Net-(D3-Pad3)") (class "Default")
      (node (ref "D3") (pin "3") (pintype "passive"))
      (node (ref "D4") (pin "3") (pintype "passive"))
      (node (ref "R7") (pin "2") (pintype "passive"))
    )
    (net (code "55") (name "Net-(D3-R)") (class "Default")
      (node (ref "D3") (pin "6") (pinfunction "R_6") (pintype "passive"))
      (node (ref "D4") (pin "6") (pinfunction "R_6") (pintype "passive"))
      (node (ref "D5") (pin "6") (pinfunction "R_6") (pintype "passive"))
      (node (ref "D6") (pin "6") (pinfunction "R_6") (pintype "passive"))
      (node (ref "Q1") (pin "3") (pinfunction "C_3") (pintype "passive"))
    )
    (net (code "56") (name "Net-(D5-Pad1)") (class "Default")
      (node (ref "D5") (pin "1") (pintype "passive"))
      (node (ref "D6") (pin "1") (pintype "passive"))
      (node (ref "R12") (pin "2") (pintype "passive"))
    )
    (net (code "57") (name "Net-(D5-Pad2)") (class "Default")
      (node (ref "D5") (pin "2") (pintype "passive"))
      (node (ref "D6") (pin "2") (pintype "passive"))
      (node (ref "R11") (pin "2") (pintype "passive"))
    )
    (net (code "58") (name "Net-(D5-Pad3)") (class "Default")
      (node (ref "D5") (pin "3") (pintype "passive"))
      (node (ref "D6") (pin "3") (pintype "passive"))
      (node (ref "R10") (pin "2") (pintype "passive"))
    )
    (net (code "59") (name "Net-(Q1-B)") (class "Default")
      (node (ref "Q1") (pin "1") (pinfunction "B_1") (pintype "passive"))
      (node (ref "R3") (pin "1") (pintype "passive"))
    )
    (net (code "60") (name "Net-(Q2-B)") (class "Default")
      (node (ref "Q2") (pin "1") (pinfunction "B_1") (pintype "passive"))
      (node (ref "R1") (pin "1") (pintype "passive"))
    )
    (net (code "61") (name "Net-(Q3-B)") (class "Default")
      (node (ref "Q3") (pin "1") (pinfunction "B_1") (pintype "passive"))
      (node (ref "R2") (pin "1") (pintype "passive"))
    )
    (net (code "62") (name "Net-(Q4-G)") (class "Default")
      (node (ref "Q4") (pin "1") (pinfunction "G_1") (pintype "passive"))
      (node (ref "Q7") (pin "3") (pinfunction "C_3") (pintype "passive"))
      (node (ref "R13") (pin "2") (pintype "passive"))
    )
    (net (code "63") (name "Net-(Q5-G)") (class "Default")
      (node (ref "Q5") (pin "1") (pinfunction "G_1") (pintype "passive"))
      (node (ref "Q8") (pin "3") (pinfunction "C_3") (pintype "passive"))
      (node (ref "R14") (pin "2") (pintype "passive"))
    )
    (net (code "64") (name "Net-(Q6-G)") (class "Default")
      (node (ref "Q6") (pin "1") (pinfunction "G_1") (pintype "passive"))
      (node (ref "Q9") (pin "3") (pinfunction "C_3") (pintype "passive"))
      (node (ref "R15") (pin "2") (pintype "passive"))
    )
    (net (code "65") (name "Net-(Q7-B)") (class "Default")
      (node (ref "Q7") (pin "1") (pinfunction "B_1") (pintype "passive"))
      (node (ref "R17") (pin "1") (pintype "passive"))
    )
    (net (code "66") (name "Net-(Q8-B)") (class "Default")
      (node (ref "Q8") (pin "1") (pinfunction "B_1") (pintype "passive"))
      (node (ref "R18") (pin "1") (pintype "passive"))
    )
    (net (code "67") (name "Net-(Q9-B)") (class "Default")
      (node (ref "Q9") (pin "1") (pinfunction "B_1") (pintype "passive"))
      (node (ref "R19") (pin "1") (pintype "passive"))
    )
    (net (code "68") (name "Net-(Q10-G)") (class "Default")
      (node (ref "Q10") (pin "1") (pinfunction "G_1") (pintype "passive"))
      (node (ref "Q13") (pin "3") (pinfunction "C_3") (pintype "passive"))
      (node (ref "R23") (pin "2") (pintype "passive"))
    )
    (net (code "69") (name "Net-(Q11-G)") (class "Default")
      (node (ref "Q11") (pin "1") (pinfunction "G_1") (pintype "passive"))
      (node (ref "Q14") (pin "3") (pinfunction "C_3") (pintype "passive"))
      (node (ref "R24") (pin "2") (pintype "passive"))
    )
    (net (code "70") (name "Net-(Q12-D)") (class "Default")
      (node (ref "LED-6") (pin "1") (pinfunction "1_1") (pintype "passive"))
      (node (ref "Q12") (pin "3") (pinfunction "D_3") (pintype "passive"))
    )
    (net (code "71") (name "Net-(Q12-G)") (class "Default")
      (node (ref "Q12") (pin "1") (pinfunction "G_1") (pintype "passive"))
      (node (ref "Q15") (pin "3") (pinfunction "C_3") (pintype "passive"))
      (node (ref "R25") (pin "2") (pintype "passive"))
    )
    (net (code "72") (name "Net-(Q13-B)") (class "Default")
      (node (ref "Q13") (pin "1") (pinfunction "B_1") (pintype "passive"))
      (node (ref "R26") (pin "1") (pintype "passive"))
    )
    (net (code "73") (name "Net-(Q14-B)") (class "Default")
      (node (ref "Q14") (pin "1") (pinfunction "B_1") (pintype "passive"))
      (node (ref "R27") (pin "1") (pintype "passive"))
    )
    (net (code "74") (name "Net-(Q15-B)") (class "Default")
      (node (ref "Q15") (pin "1") (pinfunction "B_1") (pintype "passive"))
      (node (ref "R28") (pin "1") (pintype "passive"))
    )
    (net (code "75") (name "Net-(U1-CB)") (class "Default")
      (node (ref "C1") (pin "2") (pintype "passive"))
      (node (ref "U1") (pin "1") (pinfunction "CB_1") (pintype "passive"))
    )
    (net (code "76") (name "Net-(U1-FB)") (class "Default")
      (node (ref "R5") (pin "1") (pinfunction "1_1") (pintype "passive"))
      (node (ref "R6") (pin "2") (pinfunction "2_2") (pintype "passive"))
      (node (ref "U1") (pin "4") (pinfunction "FB_4") (pintype "passive"))
    )
    (net (code "77") (name "Net-(U2-XTAL2)") (class "Default")
      (node (ref "C3") (pin "1") (pintype "passive"))
      (node (ref "U2") (pin "14") (pinfunction "XTAL2_14") (pintype "passive"))
      (node (ref "Y1") (pin "2") (pintype "passive"))
    )
    (net (code "78") (name "Net-(U3-A)") (class "Default")
      (node (ref "R36") (pin "2") (pintype "passive"))
      (node (ref "R37") (pin "1") (pintype "passive"))
      (node (ref "U3") (pin "6") (pinfunction "A_6") (pintype "passive"))
    )
    (net (code "79") (name "Net-(U3-B)") (class "Default")
      (node (ref "R29") (pin "1") (pintype "passive"))
      (node (ref "R31") (pin "2") (pintype "passive"))
      (node (ref "U3") (pin "7") (pinfunction "B_7") (pintype "passive"))
    )
    (net (code "80") (name "Net-(U3-DI)") (class "Default")
      (node (ref "R35") (pin "1") (pintype "passive"))
      (node (ref "U3") (pin "4") (pinfunction "DI_4") (pintype "passive"))
    )
    (net (code "81") (name "Net-(U3-RO)") (class "Default")
      (node (ref "R34") (pin "1") (pintype "passive"))
      (node (ref "U3") (pin "1") (pinfunction "RO_1") (pintype "passive"))
    )
    (net (code "82") (name "Net-(U4-C1+)") (class "Default")
      (node (ref "C9") (pin "1") (pinfunction "1_1") (pintype "passive"))
      (node (ref "U4") (pin "1") (pinfunction "C1+_1") (pintype "bidirectional"))
    )
    (net (code "83") (name "Net-(U4-C1-)") (class "Default")
      (node (ref "C9") (pin "2") (pinfunction "2_2") (pintype "passive"))
      (node (ref "U4") (pin "3") (pinfunction "C1-_3") (pintype "bidirectional"))
    )
    (net (code "84") (name "Net-(U4-C2+)") (class "Default")
      (node (ref "C8") (pin "1") (pinfunction "1_1") (pintype "passive"))
      (node (ref "U4") (pin "4") (pinfunction "C2+_4") (pintype "bidirectional"))
    )
    (net (code "85") (name "Net-(U4-C2-)") (class "Default")
      (node (ref "C8") (pin "2") (pinfunction "2_2") (pintype "passive"))
      (node (ref "U4") (pin "5") (pinfunction "C2-_5") (pintype "bidirectional"))
    )
    (net (code "86") (name "Net-(U4-V+)") (class "Default")
      (node (ref "C7") (pin "2") (pinfunction "2_2") (pintype "passive"))
      (node (ref "U4") (pin "2") (pinfunction "V+_2") (pintype "passive"))
    )
    (net (code "87") (name "Net-(U4-V-)") (class "Default")
      (node (ref "C10") (pin "2") (pinfunction "2_2") (pintype "passive"))
      (node (ref "U4") (pin "6") (pinfunction "V-_6") (pintype "passive"))
    )
    (net (code "88") (name "VDD_+5V") (class "Default")
      (node (ref "C2") (pin "2") (pintype "passive"))
      (node (ref "C5") (pin "1") (pintype "passive"))
      (node (ref "C6") (pin "2") (pinfunction "2_2") (pintype "passive"))
      (node (ref "CT1") (pin "1") (pinfunction "1_1") (pintype "passive"))
      (node (ref "CT3") (pin "1") (pinfunction "1_1") (pintype "passive"))
      (node (ref "CT4") (pin "1") (pintype "passive"))
      (node (ref "J1") (pin "5") (pinfunction "5_5") (pintype "passive"))
      (node (ref "J1") (pin "6") (pinfunction "6_6") (pintype "passive"))
      (node (ref "L1") (pin "1") (pinfunction "1_1") (pintype "passive"))
      (node (ref "P1") (pin "18") (pinfunction "18_18") (pintype "passive"))
      (node (ref "Q1") (pin "2") (pinfunction "E_2") (pintype "passive"))
      (node (ref "Q2") (pin "2") (pinfunction "E_2") (pintype "passive"))
      (node (ref "Q3") (pin "2") (pinfunction "E_2") (pintype "passive"))
      (node (ref "R29") (pin "2") (pintype "passive"))
      (node (ref "R40") (pin "2") (pintype "passive"))
      (node (ref "R5") (pin "2") (pinfunction "2_2") (pintype "passive"))
      (node (ref "U2") (pin "38") (pinfunction "VCC_38") (pintype "passive"))
      (node (ref "U3") (pin "8") (pinfunction "VCC_8") (pintype "passive"))
      (node (ref "U4") (pin "16") (pinfunction "VCC_16") (pintype "passive"))
    )
    (net (code "89") (name "unconnected-(U1-ON{slash}OFF-Pad5)") (class "Default")
      (node (ref "U1") (pin "5") (pinfunction "ON/OFF_5") (pintype "passive"))
    )
    (net (code "90") (name "unconnected-(U2-P0.7-Pad30)") (class "Default")
      (node (ref "U2") (pin "30") (pinfunction "P0.7_30") (pintype "passive"))
    )
    (net (code "91") (name "unconnected-(U2-P1.5-Pad1)") (class "Default")
      (node (ref "U2") (pin "1") (pinfunction "P1.5_1") (pintype "passive"))
    )
    (net (code "92") (name "unconnected-(U2-P3.5-Pad11)") (class "Default")
      (node (ref "U2") (pin "11") (pinfunction "P3.5_11") (pintype "passive"))
    )
    (net (code "93") (name "unconnected-(U2-P4.0-Pad17)") (class "Default")
      (node (ref "U2") (pin "17") (pinfunction "P4.0_17") (pintype "passive"))
    )
    (net (code "94") (name "unconnected-(U2-P4.2-Pad39)") (class "Default")
      (node (ref "U2") (pin "39") (pinfunction "P4.2_39") (pintype "passive"))
    )
    (net (code "95") (name "unconnected-(U2-P4.3-Pad6)") (class "Default")
      (node (ref "U2") (pin "6") (pinfunction "P4.3_6") (pintype "passive"))
    )
    (net (code "96") (name "unconnected-(U2-P4.5-Pad27)") (class "Default")
      (node (ref "U2") (pin "27") (pinfunction "P4.5_27") (pintype "passive"))
    )
    (net (code "97") (name "unconnected-(U2-~{INT0}_P3.2-Pad8)") (class "Default")
      (node (ref "U2") (pin "8") (pinfunction "~{INT0}_P3.2_8") (pintype "passive"))
    )
    (net (code "98") (name "unconnected-(U2-~{INT1}_P3.3-Pad9)") (class "Default")
      (node (ref "U2") (pin "9") (pinfunction "~{INT1}_P3.3_9") (pintype "passive"))
    )
    (net (code "99") (name "unconnected-(U4-R1out-Pad12)") (class "Default")
      (node (ref "U4") (pin "12") (pinfunction "R1out_12") (pintype "output"))
    )
    (net (code "100") (name "unconnected-(U4-T1out-Pad14)") (class "Default")
      (node (ref "U4") (pin "14") (pinfunction "T1out_14") (pintype "output"))
    )
  )
)
